# EyeTron.net
KiCad netlist of a schematic drawn in EAGLE
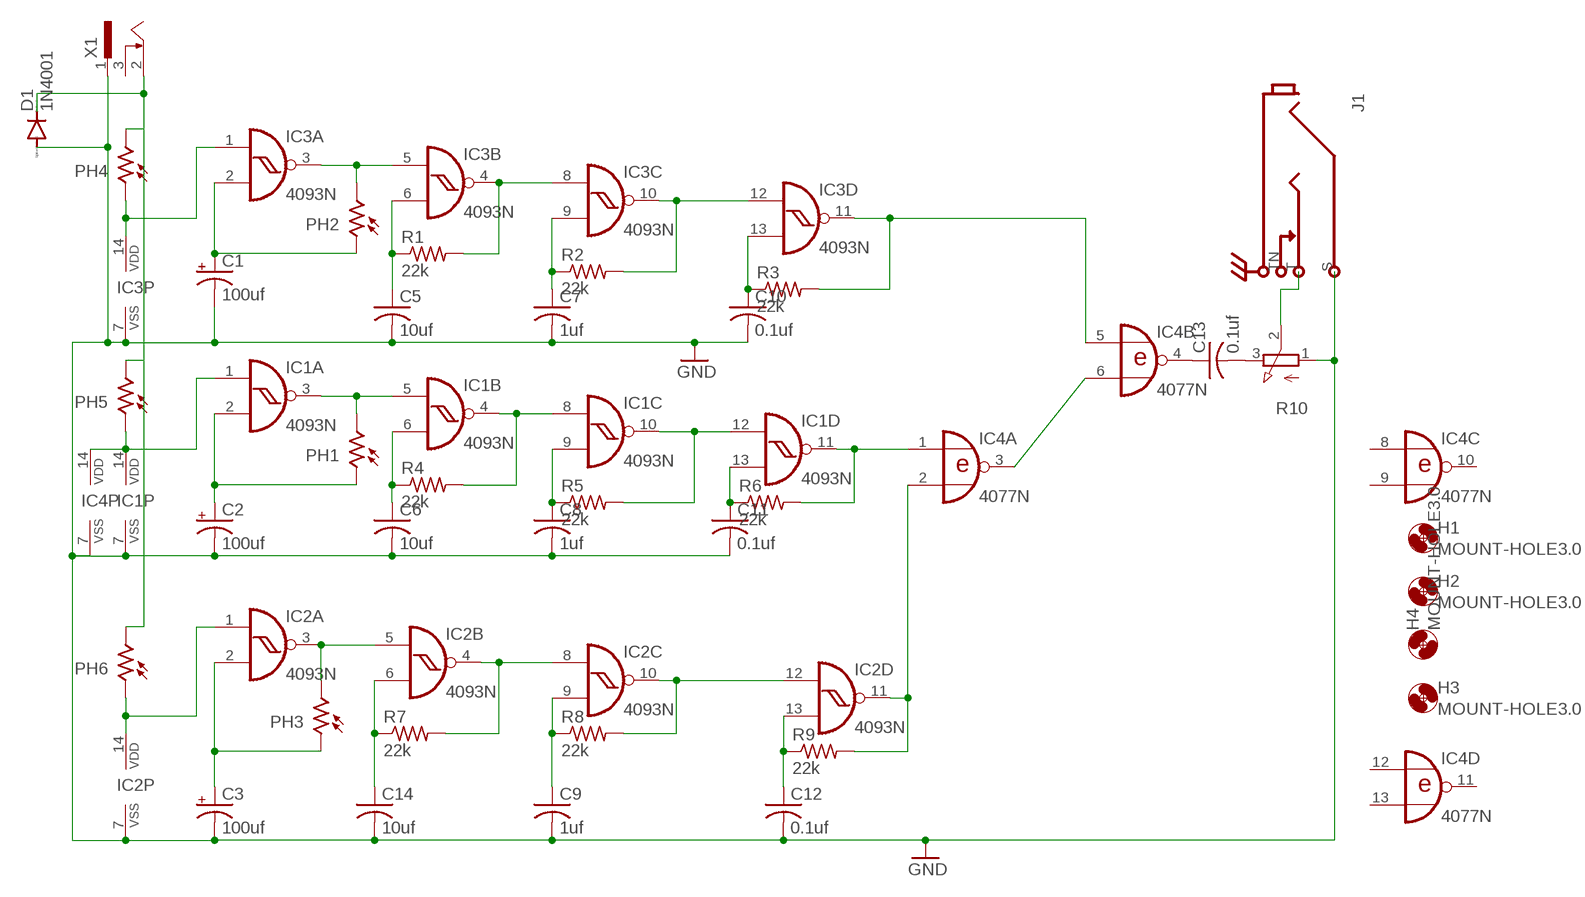
[diagram p0: schematic, sheet 1]

(export (version "E")
  (design (tool "Eeschema 10.0.6"))
  (components
    (comp (ref "C1")
      (value "100uf")
      (footprint "eagle-import:E2,5-6E")
      (libsource (lib "eagle-import") (part "CPOL-USE2,5-6E"))
    )
    (comp (ref "C2")
      (value "100uf")
      (footprint "eagle-import:E2,5-6E")
      (libsource (lib "eagle-import") (part "CPOL-USE2,5-6E"))
    )
    (comp (ref "C3")
      (value "100uf")
      (footprint "eagle-import:E2,5-6E")
      (libsource (lib "eagle-import") (part "CPOL-USE2,5-6E"))
    )
    (comp (ref "C5")
      (value "10uf")
      (footprint "eagle-import:C050-025X075")
      (libsource (lib "eagle-import") (part "C-US050-025X075"))
    )
    (comp (ref "C6")
      (value "10uf")
      (footprint "eagle-import:C050-025X075")
      (libsource (lib "eagle-import") (part "C-US050-025X075"))
    )
    (comp (ref "C7")
      (value "1uf")
      (footprint "eagle-import:C050-025X075")
      (libsource (lib "eagle-import") (part "C-US050-025X075"))
    )
    (comp (ref "C8")
      (value "1uf")
      (footprint "eagle-import:C050-025X075")
      (libsource (lib "eagle-import") (part "C-US050-025X075"))
    )
    (comp (ref "C9")
      (value "1uf")
      (footprint "eagle-import:C050-025X075")
      (libsource (lib "eagle-import") (part "C-US050-025X075"))
    )
    (comp (ref "C10")
      (value "0.1uf")
      (footprint "eagle-import:C050-025X075")
      (libsource (lib "eagle-import") (part "C-US050-025X075"))
    )
    (comp (ref "C11")
      (value "0.1uf")
      (footprint "eagle-import:C050-025X075")
      (libsource (lib "eagle-import") (part "C-US050-025X075"))
    )
    (comp (ref "C12")
      (value "0.1uf")
      (footprint "eagle-import:C050-025X075")
      (libsource (lib "eagle-import") (part "C-US050-025X075"))
    )
    (comp (ref "C13")
      (value "0.1uf")
      (footprint "eagle-import:C050-025X075")
      (libsource (lib "eagle-import") (part "C-US050-025X075"))
    )
    (comp (ref "C14")
      (value "10uf")
      (footprint "eagle-import:C050-025X075")
      (libsource (lib "eagle-import") (part "C-US050-025X075"))
    )
    (comp (ref "D1")
      (value "1N4001")
      (footprint "eagle-import:DO41-10")
      (libsource (lib "eagle-import") (part "1N4004"))
    )
    (comp (ref "H1")
      (value "MOUNT-HOLE3.0")
      (footprint "eagle-import:3,0")
      (libsource (lib "eagle-import") (part "MOUNT-HOLE3.0"))
    )
    (comp (ref "H2")
      (value "MOUNT-HOLE3.0")
      (footprint "eagle-import:3,0")
      (libsource (lib "eagle-import") (part "MOUNT-HOLE3.0"))
    )
    (comp (ref "H3")
      (value "MOUNT-HOLE3.0")
      (footprint "eagle-import:3,0")
      (libsource (lib "eagle-import") (part "MOUNT-HOLE3.0"))
    )
    (comp (ref "H4")
      (value "MOUNT-HOLE3.0")
      (footprint "eagle-import:3,0")
      (libsource (lib "eagle-import") (part "MOUNT-HOLE3.0"))
    )
    (comp (ref "IC1")
      (value "4093N")
      (footprint "eagle-import:DIL14")
      (libsource (lib "eagle-import") (part "4093N"))
    )
    (comp (ref "IC2")
      (value "4093N")
      (footprint "eagle-import:DIL14")
      (libsource (lib "eagle-import") (part "4093N"))
    )
    (comp (ref "IC3")
      (value "4093N")
      (footprint "eagle-import:DIL14")
      (fields (field (name "SPICEPREFIX") "J"))
      (libsource (lib "eagle-import") (part "4093N"))
    )
    (comp (ref "IC4")
      (value "4077N")
      (footprint "eagle-import:DIL14")
      (libsource (lib "eagle-import") (part "4077N"))
    )
    (comp (ref "J1")
      (value "MONOSW1GND")
      (footprint "eagle-import:NEUTRIK-NRJ4HM-1")
      (libsource (lib "eagle-import") (part "MONOSW1GND"))
    )
    (comp (ref "PH1")
      (value "VT90N1")
      (footprint "eagle-import:VT900")
      (libsource (lib "eagle-import") (part "VT90N1"))
    )
    (comp (ref "PH2")
      (value "VT90N1")
      (footprint "eagle-import:VT900")
      (libsource (lib "eagle-import") (part "VT90N1"))
    )
    (comp (ref "PH3")
      (value "VT90N1")
      (footprint "eagle-import:VT900")
      (libsource (lib "eagle-import") (part "VT90N1"))
    )
    (comp (ref "PH4")
      (value "VT90N1")
      (footprint "eagle-import:VT900")
      (libsource (lib "eagle-import") (part "VT90N1"))
    )
    (comp (ref "PH5")
      (value "VT90N1")
      (footprint "eagle-import:VT900")
      (libsource (lib "eagle-import") (part "VT90N1"))
    )
    (comp (ref "PH6")
      (value "VT90N1")
      (footprint "eagle-import:VT900")
      (libsource (lib "eagle-import") (part "VT90N1"))
    )
    (comp (ref "R1")
      (value "22k")
      (footprint "eagle-import:0207_7")
      (libsource (lib "eagle-import") (part "R-US_0207/7"))
    )
    (comp (ref "R2")
      (value "22k")
      (footprint "eagle-import:0207_7")
      (libsource (lib "eagle-import") (part "R-US_0207/7"))
    )
    (comp (ref "R3")
      (value "22k")
      (footprint "eagle-import:0207_7")
      (libsource (lib "eagle-import") (part "R-US_0207/7"))
    )
    (comp (ref "R4")
      (value "22k")
      (footprint "eagle-import:0207_7")
      (libsource (lib "eagle-import") (part "R-US_0207/7"))
    )
    (comp (ref "R5")
      (value "22k")
      (footprint "eagle-import:0207_7")
      (libsource (lib "eagle-import") (part "R-US_0207/7"))
    )
    (comp (ref "R6")
      (value "22k")
      (footprint "eagle-import:0207_7")
      (libsource (lib "eagle-import") (part "R-US_0207/7"))
    )
    (comp (ref "R7")
      (value "22k")
      (footprint "eagle-import:0207_7")
      (libsource (lib "eagle-import") (part "R-US_0207/7"))
    )
    (comp (ref "R8")
      (value "22k")
      (footprint "eagle-import:0207_7")
      (libsource (lib "eagle-import") (part "R-US_0207/7"))
    )
    (comp (ref "R9")
      (value "22k")
      (footprint "eagle-import:0207_7")
      (libsource (lib "eagle-import") (part "R-US_0207/7"))
    )
    (comp (ref "R10")
      (value "EVUF2L")
      (footprint "eagle-import:EVUFXL")
      (libsource (lib "eagle-import") (part "EVULF2"))
    )
    (comp (ref "X1")
      (value "SCD-014A")
      (footprint "eagle-import:SCD-014-A")
      (libsource (lib "eagle-import") (part "SCD-014A"))
    )
  )
  (nets
    (net (code "1") (name "GND") (class "Default")
      (node (ref "C1") (pin "-") (pinfunction "-_-") (pintype "passive"))
      (node (ref "C10") (pin "2") (pinfunction "2_2") (pintype "passive"))
      (node (ref "C11") (pin "2") (pinfunction "2_2") (pintype "passive"))
      (node (ref "C12") (pin "2") (pinfunction "2_2") (pintype "passive"))
      (node (ref "C14") (pin "2") (pinfunction "2_2") (pintype "passive"))
      (node (ref "C2") (pin "-") (pinfunction "-_-") (pintype "passive"))
      (node (ref "C3") (pin "-") (pinfunction "-_-") (pintype "passive"))
      (node (ref "C5") (pin "2") (pinfunction "2_2") (pintype "passive"))
      (node (ref "C6") (pin "2") (pinfunction "2_2") (pintype "passive"))
      (node (ref "C7") (pin "2") (pinfunction "2_2") (pintype "passive"))
      (node (ref "C8") (pin "2") (pinfunction "2_2") (pintype "passive"))
      (node (ref "C9") (pin "2") (pinfunction "2_2") (pintype "passive"))
      (node (ref "D1") (pin "A") (pinfunction "A_A") (pintype "passive"))
      (node (ref "IC1") (pin "7") (pinfunction "VSS_7") (pintype "power_in"))
      (node (ref "IC2") (pin "7") (pinfunction "VSS_7") (pintype "power_in"))
      (node (ref "IC3") (pin "7") (pinfunction "VSS_7") (pintype "power_in"))
      (node (ref "IC4") (pin "7") (pinfunction "VSS_7") (pintype "power_in"))
      (node (ref "J1") (pin "S") (pinfunction "S_S") (pintype "passive"))
      (node (ref "R10") (pin "1") (pinfunction "A_1") (pintype "passive"))
      (node (ref "X1") (pin "1") (pinfunction "1_1") (pintype "passive"))
    )
    (net (code "2") (name "Net-(D1-PadC)") (class "Default")
      (node (ref "D1") (pin "C") (pinfunction "C_C") (pintype "passive"))
      (node (ref "PH4") (pin "2") (pinfunction "2_2") (pintype "passive"))
      (node (ref "PH5") (pin "2") (pinfunction "2_2") (pintype "passive"))
      (node (ref "PH6") (pin "2") (pinfunction "2_2") (pintype "passive"))
      (node (ref "X1") (pin "2") (pinfunction "2_2") (pintype "passive"))
    )
    (net (code "3") (name "Net-(IC1A-I0)") (class "Default")
      (node (ref "IC1") (pin "1") (pinfunction "I0_1") (pintype "input"))
      (node (ref "IC1") (pin "14") (pinfunction "VDD_14") (pintype "power_in"))
      (node (ref "IC4") (pin "14") (pinfunction "VDD_14") (pintype "power_in"))
      (node (ref "PH5") (pin "1") (pinfunction "1_1") (pintype "passive"))
    )
    (net (code "4") (name "Net-(IC1A-I1)") (class "Default")
      (node (ref "C2") (pin "+") (pinfunction "+_+") (pintype "passive"))
      (node (ref "IC1") (pin "2") (pinfunction "I1_2") (pintype "input"))
      (node (ref "PH1") (pin "1") (pinfunction "1_1") (pintype "passive"))
    )
    (net (code "5") (name "Net-(IC1A-O)") (class "Default")
      (node (ref "IC1") (pin "3") (pinfunction "O_3") (pintype "output"))
      (node (ref "IC1") (pin "5") (pinfunction "I0_5") (pintype "input"))
      (node (ref "PH1") (pin "2") (pinfunction "2_2") (pintype "passive"))
    )
    (net (code "6") (name "Net-(IC1B-I1)") (class "Default")
      (node (ref "C6") (pin "1") (pinfunction "1_1") (pintype "passive"))
      (node (ref "IC1") (pin "6") (pinfunction "I1_6") (pintype "input"))
      (node (ref "R4") (pin "1") (pinfunction "1_1") (pintype "passive"))
    )
    (net (code "7") (name "Net-(IC1B-O)") (class "Default")
      (node (ref "IC1") (pin "4") (pinfunction "O_4") (pintype "output"))
      (node (ref "IC1") (pin "8") (pinfunction "I0_8") (pintype "input"))
      (node (ref "R4") (pin "2") (pinfunction "2_2") (pintype "passive"))
    )
    (net (code "8") (name "Net-(IC1C-I1)") (class "Default")
      (node (ref "C8") (pin "1") (pinfunction "1_1") (pintype "passive"))
      (node (ref "IC1") (pin "9") (pinfunction "I1_9") (pintype "input"))
      (node (ref "R5") (pin "1") (pinfunction "1_1") (pintype "passive"))
    )
    (net (code "9") (name "Net-(IC1C-O)") (class "Default")
      (node (ref "IC1") (pin "10") (pinfunction "O_10") (pintype "output"))
      (node (ref "IC1") (pin "12") (pinfunction "I0_12") (pintype "input"))
      (node (ref "R5") (pin "2") (pinfunction "2_2") (pintype "passive"))
    )
    (net (code "10") (name "Net-(IC1D-I1)") (class "Default")
      (node (ref "C11") (pin "1") (pinfunction "1_1") (pintype "passive"))
      (node (ref "IC1") (pin "13") (pinfunction "I1_13") (pintype "input"))
      (node (ref "R6") (pin "1") (pinfunction "1_1") (pintype "passive"))
    )
    (net (code "11") (name "Net-(IC1D-O)") (class "Default")
      (node (ref "IC1") (pin "11") (pinfunction "O_11") (pintype "output"))
      (node (ref "IC4") (pin "1") (pinfunction "I0_1") (pintype "input"))
      (node (ref "R6") (pin "2") (pinfunction "2_2") (pintype "passive"))
    )
    (net (code "12") (name "Net-(IC2A-I0)") (class "Default")
      (node (ref "IC2") (pin "1") (pinfunction "I0_1") (pintype "input"))
      (node (ref "IC2") (pin "14") (pinfunction "VDD_14") (pintype "power_in"))
      (node (ref "PH6") (pin "1") (pinfunction "1_1") (pintype "passive"))
    )
    (net (code "13") (name "Net-(IC2A-I1)") (class "Default")
      (node (ref "C3") (pin "+") (pinfunction "+_+") (pintype "passive"))
      (node (ref "IC2") (pin "2") (pinfunction "I1_2") (pintype "input"))
      (node (ref "PH3") (pin "1") (pinfunction "1_1") (pintype "passive"))
    )
    (net (code "14") (name "Net-(IC2A-O)") (class "Default")
      (node (ref "IC2") (pin "3") (pinfunction "O_3") (pintype "output"))
      (node (ref "IC2") (pin "5") (pinfunction "I0_5") (pintype "input"))
      (node (ref "PH3") (pin "2") (pinfunction "2_2") (pintype "passive"))
    )
    (net (code "15") (name "Net-(IC2B-I1)") (class "Default")
      (node (ref "C14") (pin "1") (pinfunction "1_1") (pintype "passive"))
      (node (ref "IC2") (pin "6") (pinfunction "I1_6") (pintype "input"))
      (node (ref "R7") (pin "1") (pinfunction "1_1") (pintype "passive"))
    )
    (net (code "16") (name "Net-(IC2B-O)") (class "Default")
      (node (ref "IC2") (pin "4") (pinfunction "O_4") (pintype "output"))
      (node (ref "IC2") (pin "8") (pinfunction "I0_8") (pintype "input"))
      (node (ref "R7") (pin "2") (pinfunction "2_2") (pintype "passive"))
    )
    (net (code "17") (name "Net-(IC2C-I1)") (class "Default")
      (node (ref "C9") (pin "1") (pinfunction "1_1") (pintype "passive"))
      (node (ref "IC2") (pin "9") (pinfunction "I1_9") (pintype "input"))
      (node (ref "R8") (pin "1") (pinfunction "1_1") (pintype "passive"))
    )
    (net (code "18") (name "Net-(IC2C-O)") (class "Default")
      (node (ref "IC2") (pin "10") (pinfunction "O_10") (pintype "output"))
      (node (ref "IC2") (pin "12") (pinfunction "I0_12") (pintype "input"))
      (node (ref "R8") (pin "2") (pinfunction "2_2") (pintype "passive"))
    )
    (net (code "19") (name "Net-(IC2D-I1)") (class "Default")
      (node (ref "C12") (pin "1") (pinfunction "1_1") (pintype "passive"))
      (node (ref "IC2") (pin "13") (pinfunction "I1_13") (pintype "input"))
      (node (ref "R9") (pin "1") (pinfunction "1_1") (pintype "passive"))
    )
    (net (code "20") (name "Net-(IC2D-O)") (class "Default")
      (node (ref "IC2") (pin "11") (pinfunction "O_11") (pintype "output"))
      (node (ref "IC4") (pin "2") (pinfunction "I1_2") (pintype "input"))
      (node (ref "R9") (pin "2") (pinfunction "2_2") (pintype "passive"))
    )
    (net (code "21") (name "Net-(IC3A-I0)") (class "Default")
      (node (ref "IC3") (pin "1") (pinfunction "I0_1") (pintype "input"))
      (node (ref "IC3") (pin "14") (pinfunction "VDD_14") (pintype "power_in"))
      (node (ref "PH4") (pin "1") (pinfunction "1_1") (pintype "passive"))
    )
    (net (code "22") (name "Net-(IC3A-I1)") (class "Default")
      (node (ref "C1") (pin "+") (pinfunction "+_+") (pintype "passive"))
      (node (ref "IC3") (pin "2") (pinfunction "I1_2") (pintype "input"))
      (node (ref "PH2") (pin "1") (pinfunction "1_1") (pintype "passive"))
    )
    (net (code "23") (name "Net-(IC3A-O)") (class "Default")
      (node (ref "IC3") (pin "3") (pinfunction "O_3") (pintype "output"))
      (node (ref "IC3") (pin "5") (pinfunction "I0_5") (pintype "input"))
      (node (ref "PH2") (pin "2") (pinfunction "2_2") (pintype "passive"))
    )
    (net (code "24") (name "Net-(IC3B-I1)") (class "Default")
      (node (ref "C5") (pin "1") (pinfunction "1_1") (pintype "passive"))
      (node (ref "IC3") (pin "6") (pinfunction "I1_6") (pintype "input"))
      (node (ref "R1") (pin "1") (pinfunction "1_1") (pintype "passive"))
    )
    (net (code "25") (name "Net-(IC3B-O)") (class "Default")
      (node (ref "IC3") (pin "4") (pinfunction "O_4") (pintype "output"))
      (node (ref "IC3") (pin "8") (pinfunction "I0_8") (pintype "input"))
      (node (ref "R1") (pin "2") (pinfunction "2_2") (pintype "passive"))
    )
    (net (code "26") (name "Net-(IC3C-I1)") (class "Default")
      (node (ref "C7") (pin "1") (pinfunction "1_1") (pintype "passive"))
      (node (ref "IC3") (pin "9") (pinfunction "I1_9") (pintype "input"))
      (node (ref "R2") (pin "1") (pinfunction "1_1") (pintype "passive"))
    )
    (net (code "27") (name "Net-(IC3C-O)") (class "Default")
      (node (ref "IC3") (pin "10") (pinfunction "O_10") (pintype "output"))
      (node (ref "IC3") (pin "12") (pinfunction "I0_12") (pintype "input"))
      (node (ref "R2") (pin "2") (pinfunction "2_2") (pintype "passive"))
    )
    (net (code "28") (name "Net-(IC3D-I1)") (class "Default")
      (node (ref "C10") (pin "1") (pinfunction "1_1") (pintype "passive"))
      (node (ref "IC3") (pin "13") (pinfunction "I1_13") (pintype "input"))
      (node (ref "R3") (pin "1") (pinfunction "1_1") (pintype "passive"))
    )
    (net (code "29") (name "Net-(IC3D-O)") (class "Default")
      (node (ref "IC3") (pin "11") (pinfunction "O_11") (pintype "output"))
      (node (ref "IC4") (pin "5") (pinfunction "I0_5") (pintype "input"))
      (node (ref "R3") (pin "2") (pinfunction "2_2") (pintype "passive"))
    )
    (net (code "30") (name "Net-(IC4A-O)") (class "Default")
      (node (ref "IC4") (pin "3") (pinfunction "O_3") (pintype "output"))
      (node (ref "IC4") (pin "6") (pinfunction "I1_6") (pintype "input"))
    )
    (net (code "31") (name "Net-(IC4B-O)") (class "Default")
      (node (ref "C13") (pin "1") (pinfunction "1_1") (pintype "passive"))
      (node (ref "IC4") (pin "4") (pinfunction "O_4") (pintype "output"))
    )
    (net (code "32") (name "Net-(R10-E)") (class "Default")
      (node (ref "C13") (pin "2") (pinfunction "2_2") (pintype "passive"))
      (node (ref "R10") (pin "3") (pinfunction "E_3") (pintype "passive"))
    )
    (net (code "33") (name "Net-(R10-S)") (class "Default")
      (node (ref "J1") (pin "T") (pinfunction "T_T") (pintype "passive"))
      (node (ref "R10") (pin "2") (pinfunction "S_2") (pintype "passive"))
    )
    (net (code "34") (name "unconnected-(IC4C-I0-Pad8)") (class "Default")
      (node (ref "IC4") (pin "8") (pinfunction "I0_8") (pintype "input"))
    )
    (net (code "35") (name "unconnected-(IC4C-I1-Pad9)") (class "Default")
      (node (ref "IC4") (pin "9") (pinfunction "I1_9") (pintype "input"))
    )
    (net (code "36") (name "unconnected-(IC4C-O-Pad10)") (class "Default")
      (node (ref "IC4") (pin "10") (pinfunction "O_10") (pintype "output"))
    )
    (net (code "37") (name "unconnected-(IC4D-I0-Pad12)") (class "Default")
      (node (ref "IC4") (pin "12") (pinfunction "I0_12") (pintype "input"))
    )
    (net (code "38") (name "unconnected-(IC4D-I1-Pad13)") (class "Default")
      (node (ref "IC4") (pin "13") (pinfunction "I1_13") (pintype "input"))
    )
    (net (code "39") (name "unconnected-(IC4D-O-Pad11)") (class "Default")
      (node (ref "IC4") (pin "11") (pinfunction "O_11") (pintype "output"))
    )
    (net (code "40") (name "unconnected-(J1-PadTN)") (class "Default")
      (node (ref "J1") (pin "TN") (pinfunction "TN_TN") (pintype "passive"))
    )
    (net (code "41") (name "unconnected-(X1-Pad3)") (class "Default")
      (node (ref "X1") (pin "3") (pinfunction "3_3") (pintype "passive"))
    )
  )
)
